# Sheet1.net
KiCad netlist of a schematic drawn in Altium Designer
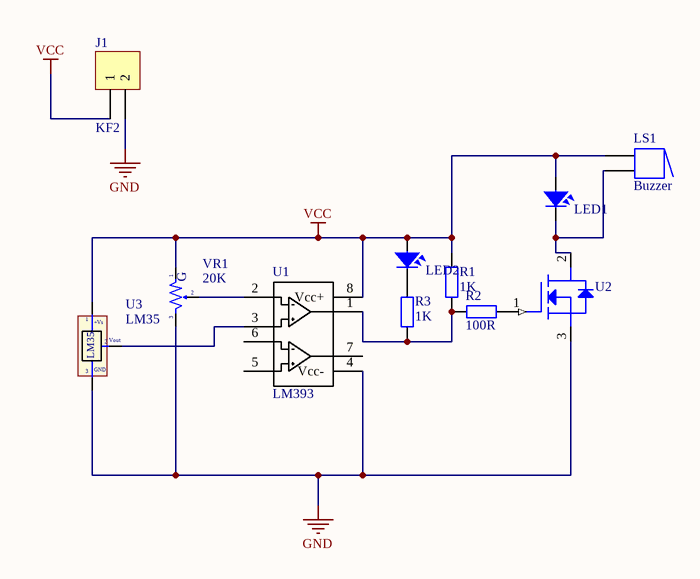
[diagram p0: Sheet1.SchDoc]

(export (version "E")
  (design (tool "Eeschema 10.0.6"))
  (components
    (comp (ref "J1")
      (value "KF2")
      (footprint "KF2-3.5")
      (fields
        (field (name "MANUFACTURER") "Würth Elektronik eiSos GmbH")
        (field (name "PARTNO") "691103110002")
        (field (name "CREATED BY") "Karrer Zheng")
      )
      (libsource (lib "LIBRARY") (part "KF2"))
    )
    (comp (ref "LED1")
      (value "LED")
      (footprint "LED-5MM-RED")
      (description "LED Single colour Green and Red")
      (libsource (lib "LIBRARY") (part "LED"))
    )
    (comp (ref "LED2")
      (value "LED")
      (footprint "LED-5MM-GREEN")
      (description "LED Single colour Green and Red")
      (libsource (lib "LIBRARY") (part "LED"))
    )
    (comp (ref "LS1")
      (value "Buzzer")
      (footprint "Buzzer")
      (description "Magnetic Transducer Buzzer")
      (fields (field (name "PUBLISHER") "Altium Limited"))
      (libsource (lib "hphonglib") (part "Buzzer"))
    )
    (comp (ref "R1")
      (value "1K")
      (footprint "R1/4W")
      (description "Resistor 1/4W")
      (libsource (lib "hphonglib") (part "R1/4W"))
    )
    (comp (ref "R2")
      (value "100R")
      (footprint "R1/4W")
      (description "Resistor 1/4W")
      (libsource (lib "hphonglib") (part "R1/4W"))
    )
    (comp (ref "R3")
      (value "1K")
      (footprint "R1/4W")
      (description "Resistor 1/4W")
      (libsource (lib "hphonglib") (part "R1/4W"))
    )
    (comp (ref "U1")
      (value "LM393")
      (footprint "DIP8")
      (description "IC DUAL COMPARATOR")
      (libsource (lib "LIBRARY") (part "LM393"))
    )
    (comp (ref "U2")
      (value "IRF540_1")
      (footprint "TO-220N")
      (description "IRF9540 - N-CHANNEL POWER MOSFETS")
      (fields (field (name "PUBLISHER") "Hoang Nguyen"))
      (libsource (lib "hphonglib") (part "IRF540_1"))
    )
    (comp (ref "U3")
      (value "LM35")
      (footprint "TO92-123")
      (description "Teminal")
      (libsource (lib "LIBRARY") (part "LM35"))
    )
    (comp (ref "VR1")
      (value "20K")
      (footprint "VR-S2")
      (description "Var Resistor")
      (libsource (lib "LIBRARY") (part "VR-S"))
    )
  )
  (nets
    (net (code "1") (name "GND") (class "Default")
      (node (ref "J1") (pin "2") (pinfunction "2_2") (pintype "passive"))
      (node (ref "U1") (pin "4") (pinfunction "Vcc-_4") (pintype "passive"))
      (node (ref "U2") (pin "3") (pinfunction "S_3") (pintype "passive"))
      (node (ref "U3") (pin "3") (pinfunction "-_3") (pintype "passive"))
      (node (ref "VR1") (pin "3") (pinfunction "3_3") (pintype "passive"))
    )
    (net (code "2") (name "Net-(LED2-Pad2)") (class "Default")
      (node (ref "LED2") (pin "2") (pinfunction "2_2") (pintype "passive"))
      (node (ref "R3") (pin "1") (pinfunction "1_1") (pintype "passive"))
    )
    (net (code "3") (name "Net-(R1-Pad1)") (class "Default")
      (node (ref "R1") (pin "1") (pinfunction "1_1") (pintype "passive"))
      (node (ref "R2") (pin "1") (pinfunction "1_1") (pintype "passive"))
      (node (ref "R3") (pin "2") (pinfunction "2_2") (pintype "passive"))
      (node (ref "U1") (pin "1") (pintype "passive"))
    )
    (net (code "4") (name "Net-(U1-Pad2)") (class "Default")
      (node (ref "U1") (pin "2") (pintype "passive"))
      (node (ref "VR1") (pin "2") (pinfunction "2_2") (pintype "passive"))
    )
    (net (code "5") (name "Net-(U2-D)") (class "Default")
      (node (ref "LED1") (pin "2") (pinfunction "2_2") (pintype "passive"))
      (node (ref "LS1") (pin "2") (pinfunction "2_2") (pintype "passive"))
      (node (ref "U2") (pin "2") (pinfunction "D_2") (pintype "passive"))
    )
    (net (code "6") (name "Net-(U2-G)") (class "Default")
      (node (ref "R2") (pin "2") (pinfunction "2_2") (pintype "passive"))
      (node (ref "U2") (pin "1") (pinfunction "G_1") (pintype "input"))
    )
    (net (code "7") (name "Net-(U3-Vout)") (class "Default")
      (node (ref "U1") (pin "3") (pintype "passive"))
      (node (ref "U3") (pin "2") (pinfunction "Vout_2") (pintype "passive"))
    )
    (net (code "8") (name "VCC") (class "Default")
      (node (ref "J1") (pin "1") (pinfunction "1_1") (pintype "passive"))
      (node (ref "LED1") (pin "1") (pinfunction "1_1") (pintype "passive"))
      (node (ref "LED2") (pin "1") (pinfunction "1_1") (pintype "passive"))
      (node (ref "LS1") (pin "1") (pinfunction "1_1") (pintype "passive"))
      (node (ref "R1") (pin "2") (pinfunction "2_2") (pintype "passive"))
      (node (ref "U1") (pin "8") (pinfunction "Vcc+_8") (pintype "passive"))
      (node (ref "U3") (pin "1") (pinfunction "+Vs_1") (pintype "passive"))
      (node (ref "VR1") (pin "1") (pinfunction "1_1") (pintype "passive"))
    )
    (net (code "9") (name "unconnected-(U1-Pad5)") (class "Default")
      (node (ref "U1") (pin "5") (pintype "passive"))
    )
    (net (code "10") (name "unconnected-(U1-Pad6)") (class "Default")
      (node (ref "U1") (pin "6") (pintype "passive"))
    )
    (net (code "11") (name "unconnected-(U1-Pad7)") (class "Default")
      (node (ref "U1") (pin "7") (pintype "passive"))
    )
  )
)
